# DiffAmp.net
KiCad netlist of a schematic drawn in Altium Designer
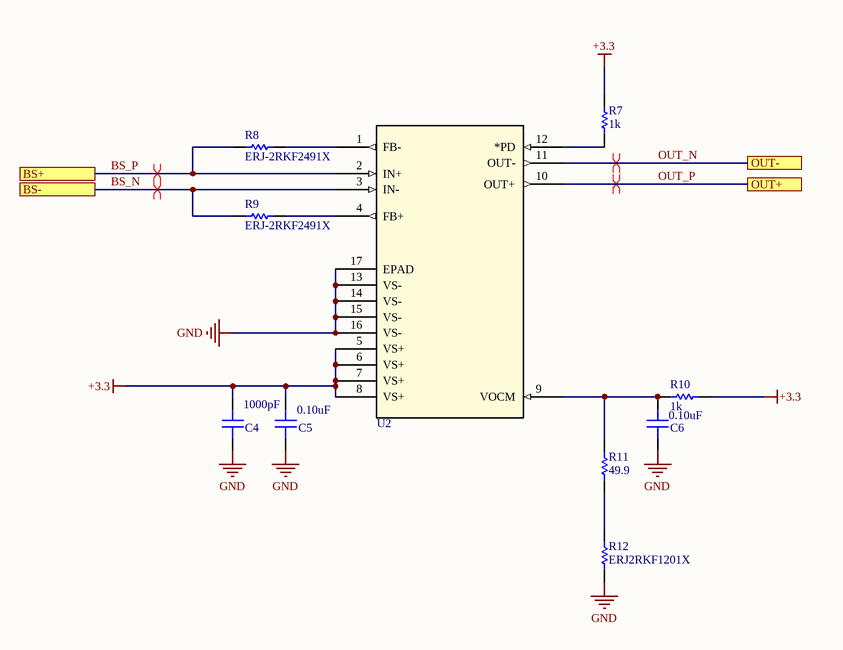
[diagram p0: DiffAmp.SchDoc]

(export (version "E")
  (design (tool "Eeschema 10.0.6"))
  (components
    (comp (ref "C4")
      (value "1000pF")
      (footprint "CAP 0402/1005")
      (description "CAP CER 1000PF 25V X7R 0402")
      (fields (field (name "PART NUMBER") "C0402C102K3RACTU") (field (name "MANUFACTURER") "Kemet"))
      (libsource (lib "Celestial Library Database") (part "Capacitor"))
    )
    (comp (ref "C5")
      (value "0.10uF")
      (footprint "CAP 0402/1005")
      (description "CAP CER 0.1UF 16V X7R 0402")
      (fields
        (field (name "PART NUMBER") "GRM155R71C104JA88D")
        (field (name "MANUFACTURER") "Murata Electronics North America")
      )
      (libsource (lib "Celestial Library Database") (part "Capacitor"))
    )
    (comp (ref "C6")
      (value "0.10uF")
      (footprint "CAP 0402/1005")
      (description "CAP CER 0.1UF 16V X7R 0402")
      (fields
        (field (name "PART NUMBER") "GRM155R71C104JA88D")
        (field (name "MANUFACTURER") "Murata Electronics North America")
      )
      (libsource (lib "Celestial Library Database") (part "Capacitor"))
    )
    (comp (ref "R7")
      (value "1k")
      (footprint "RESC1005X40X25NL05T05")
      (description "Chip Resistor, 1 KOhm, +/- 1%, 100 mW, -55 to 155 degC, 0402 (1005 Metric), RoHS, Tape and Reel")
      (fields (field (name "PARTNUMBER") "ERJ-2RKF1001X") (field (name "MANUFACTURER") "Basic Passives"))
      (libsource (lib "Altium Content Vault") (part "RES-2"))
    )
    (comp (ref "R8")
      (value "ERJ-2RKF2491X")
      (footprint "RESC1005X40X25ML05T05")
      (fields (field (name "MANUFACTURER") "Panasonic"))
      (libsource (lib "Altium Content Vault") (part "RES"))
    )
    (comp (ref "R9")
      (value "ERJ-2RKF2491X")
      (footprint "RESC1005X40X25ML05T05")
      (description "2.49k")
      (fields (field (name "MANUFACTURER") "Panasonic"))
      (libsource (lib "Altium Content Vault") (part "RES"))
    )
    (comp (ref "R10")
      (value "1k")
      (footprint "RESC1005X40X25NL05T05")
      (description "Chip Resistor, 1 KOhm, +/- 1%, 100 mW, -55 to 155 degC, 0402 (1005 Metric), RoHS, Tape and Reel")
      (fields (field (name "PARTNUMBER") "ERJ-2RKF1001X") (field (name "MANUFACTURER") "Basic Passives"))
      (libsource (lib "Altium Content Vault") (part "RES-2"))
    )
    (comp (ref "R11")
      (value "49.9")
      (footprint "RESC1005X40X25NL05T05")
      (fields (field (name "MANUFACTURER") "Panasonic") (field (name "PART NUMBER") "ERJ-2RKF49R9X"))
      (libsource (lib "Altium Content Vault") (part "RES"))
    )
    (comp (ref "R12")
      (value "ERJ2RKF1201X")
      (footprint "RESC1005X40X25ML05T05")
      (fields (field (name "MANUFACTURER") "Panasonic"))
      (libsource (lib "Altium Content Vault") (part "RES"))
    )
    (comp (ref "U2")
      (value "THS4541IRGTT")
      (footprint "TI VQFN-16 (3x3)")
      (description "IC OPAMP DIFF 1 CIRCUIT 16VQFN")
      (fields
        (field (name "MANUFACTURER") "Texas Instruments")
        (field (name "COPYRIGHT") "Copyright (C) 2018 Accelerated Designs. All rights reserved")
      )
      (libsource (lib "Celestial Library Database") (part "THS4541IRGTT"))
    )
  )
  (nets
    (net (code "1") (name "+3.3") (class "Default")
      (node (ref "C4") (pin "2") (pinfunction "2_2") (pintype "passive"))
      (node (ref "C5") (pin "2") (pinfunction "2_2") (pintype "passive"))
      (node (ref "R10") (pin "1") (pinfunction "1_1") (pintype "passive"))
      (node (ref "R7") (pin "2") (pinfunction "2_2") (pintype "passive"))
      (node (ref "U2") (pin "5") (pinfunction "VS+_5") (pintype "power_in"))
      (node (ref "U2") (pin "6") (pinfunction "VS+_6") (pintype "power_in"))
      (node (ref "U2") (pin "7") (pinfunction "VS+_7") (pintype "power_in"))
      (node (ref "U2") (pin "8") (pinfunction "VS+_8") (pintype "power_in"))
    )
    (net (code "2") (name "/BS_N") (class "Default")
      (node (ref "R9") (pin "1") (pinfunction "1_1") (pintype "passive"))
      (node (ref "U2") (pin "3") (pinfunction "IN-_3") (pintype "input"))
    )
    (net (code "3") (name "/BS_P") (class "Default")
      (node (ref "R8") (pin "1") (pinfunction "1_1") (pintype "passive"))
      (node (ref "U2") (pin "2") (pinfunction "IN+_2") (pintype "input"))
    )
    (net (code "4") (name "/OUT_N") (class "Default")
      (node (ref "U2") (pin "11") (pinfunction "OUT-_11") (pintype "output"))
    )
    (net (code "5") (name "/OUT_P") (class "Default")
      (node (ref "U2") (pin "10") (pinfunction "OUT+_10") (pintype "output"))
    )
    (net (code "6") (name "GND") (class "Default")
      (node (ref "C4") (pin "1") (pinfunction "1_1") (pintype "passive"))
      (node (ref "C5") (pin "1") (pinfunction "1_1") (pintype "passive"))
      (node (ref "C6") (pin "1") (pinfunction "1_1") (pintype "passive"))
      (node (ref "R12") (pin "1") (pinfunction "1_1") (pintype "passive"))
      (node (ref "U2") (pin "13") (pinfunction "VS-_13") (pintype "power_in"))
      (node (ref "U2") (pin "14") (pinfunction "VS-_14") (pintype "power_in"))
      (node (ref "U2") (pin "15") (pinfunction "VS-_15") (pintype "power_in"))
      (node (ref "U2") (pin "16") (pinfunction "VS-_16") (pintype "power_in"))
      (node (ref "U2") (pin "17") (pinfunction "EPAD_17") (pintype "passive"))
    )
    (net (code "7") (name "Net-(R11-Pad1)") (class "Default")
      (node (ref "R11") (pin "1") (pinfunction "1_1") (pintype "passive"))
      (node (ref "R12") (pin "2") (pinfunction "2_2") (pintype "passive"))
    )
    (net (code "8") (name "Net-(U2-*PD)") (class "Default")
      (node (ref "R7") (pin "1") (pinfunction "1_1") (pintype "passive"))
      (node (ref "U2") (pin "12") (pinfunction "*PD_12") (pintype "input"))
    )
    (net (code "9") (name "Net-(U2-FB+)") (class "Default")
      (node (ref "R9") (pin "2") (pinfunction "2_2") (pintype "passive"))
      (node (ref "U2") (pin "4") (pinfunction "FB+_4") (pintype "output"))
    )
    (net (code "10") (name "Net-(U2-FB-)") (class "Default")
      (node (ref "R8") (pin "2") (pinfunction "2_2") (pintype "passive"))
      (node (ref "U2") (pin "1") (pinfunction "FB-_1") (pintype "output"))
    )
    (net (code "11") (name "Net-(U2-VOCM)") (class "Default")
      (node (ref "C6") (pin "2") (pinfunction "2_2") (pintype "passive"))
      (node (ref "R10") (pin "2") (pinfunction "2_2") (pintype "passive"))
      (node (ref "R11") (pin "2") (pinfunction "2_2") (pintype "passive"))
      (node (ref "U2") (pin "9") (pinfunction "VOCM_9") (pintype "input"))
    )
  )
)
